# SolarTracker-EagleProject.net
KiCad netlist of a schematic drawn in EAGLE
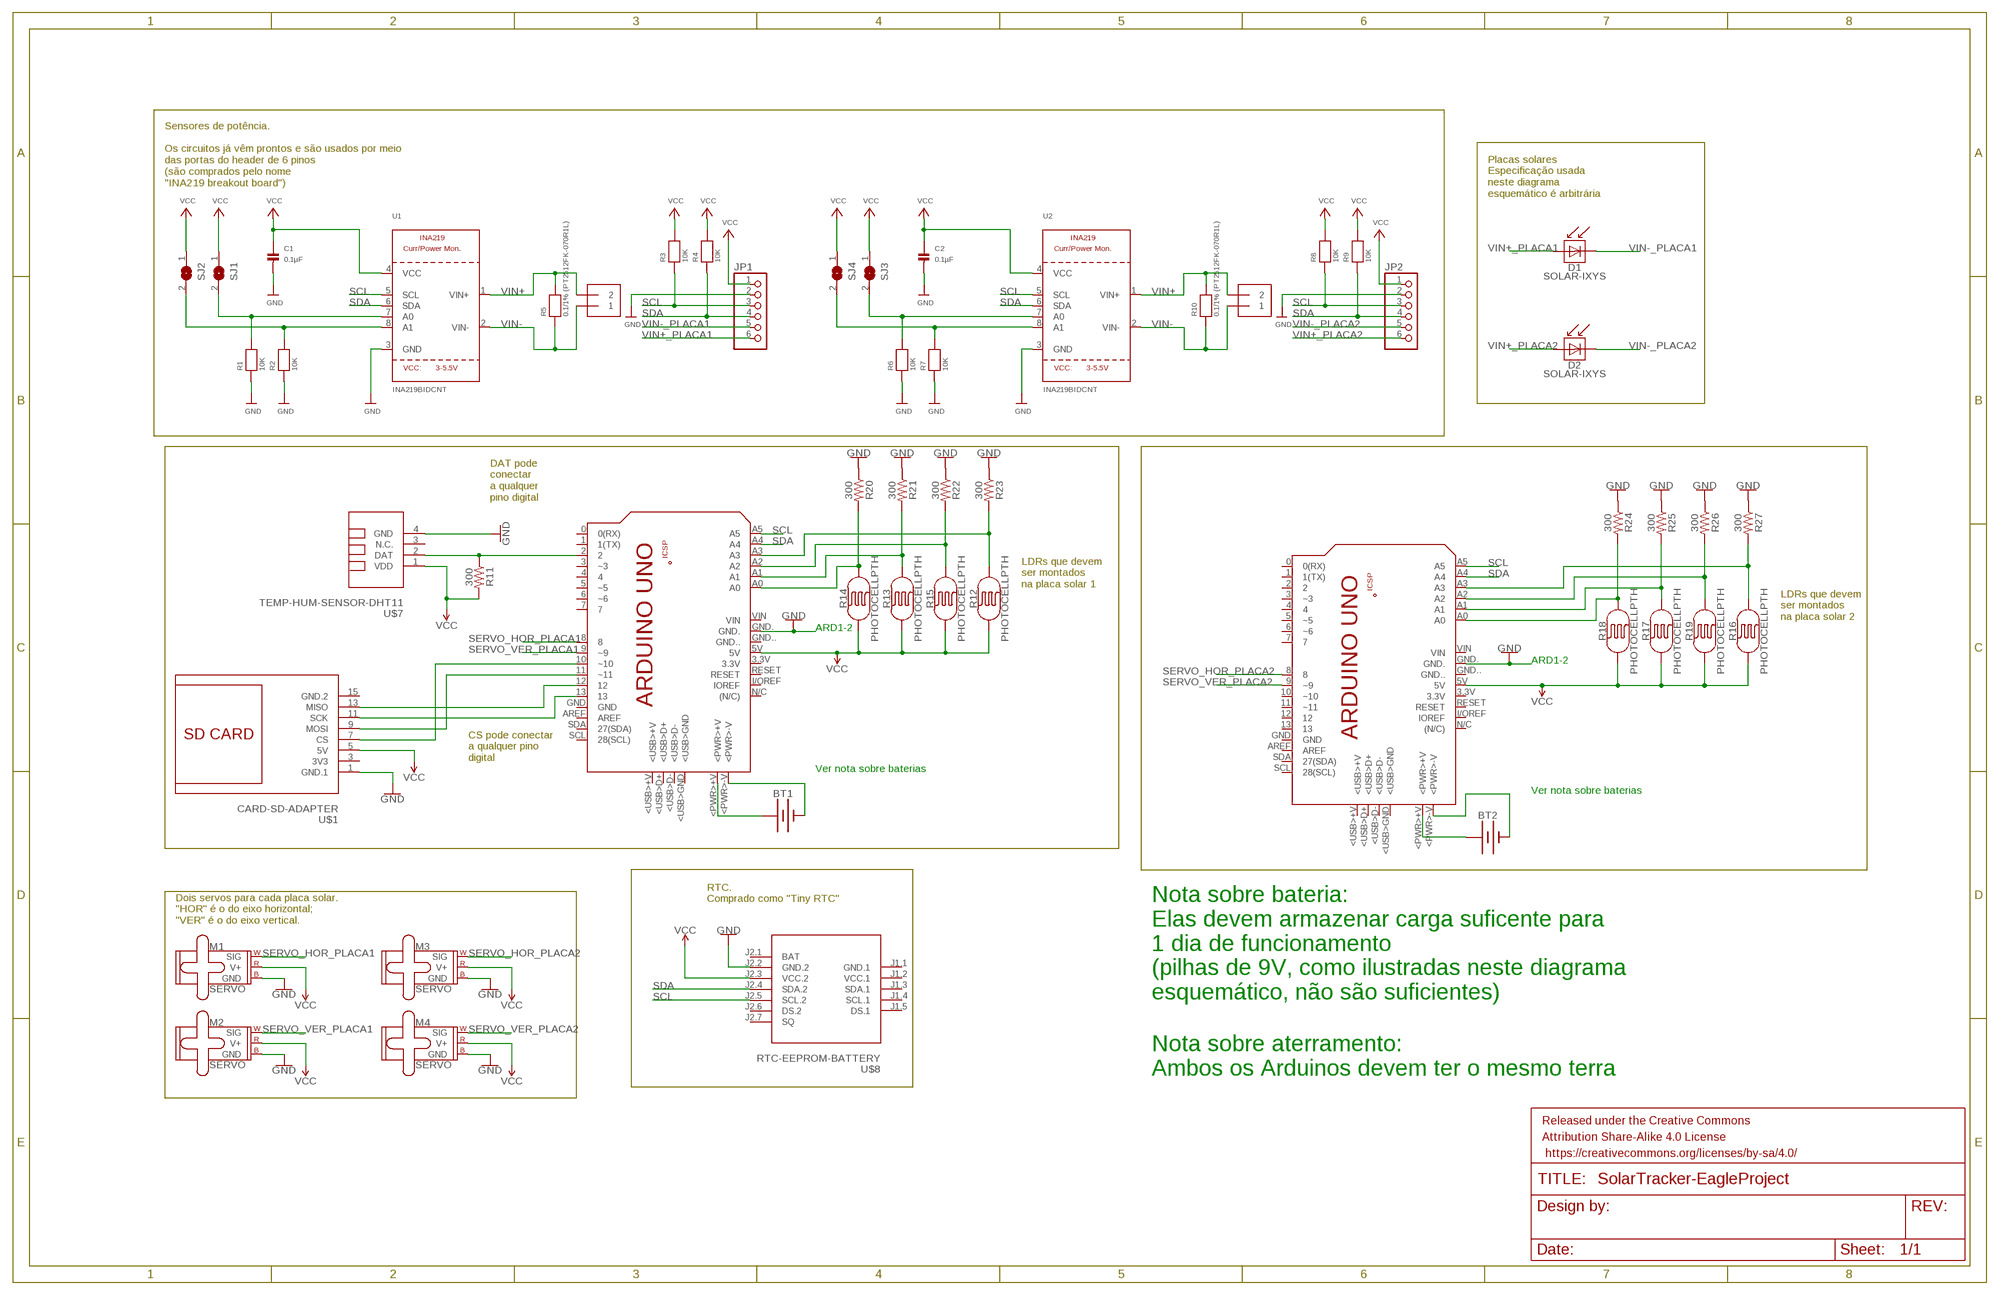
[diagram p0: schematic, sheet 1]

(export (version "E")
  (design (tool "Eeschema 10.0.6"))
  (components
    (comp (ref "BT1")
      (value "BATTERY-9V")
      (footprint "eagle-import:BATTCON_9V")
      (libsource (lib "eagle-import") (part "BATTERY-9V"))
    )
    (comp (ref "BT2")
      (value "BATTERY-9V")
      (footprint "eagle-import:BATTCON_9V")
      (libsource (lib "eagle-import") (part "BATTERY-9V"))
    )
    (comp (ref "C1")
      (value "0.1µF")
      (footprint "eagle-import:0805")
      (libsource (lib "eagle-import") (part "CAP_CERAMIC0805"))
    )
    (comp (ref "C2")
      (value "0.1µF")
      (footprint "eagle-import:0805")
      (libsource (lib "eagle-import") (part "CAP_CERAMIC0805"))
    )
    (comp (ref "D1")
      (value "SOLAR-IXYS")
      (footprint "eagle-import:SOIC-8")
      (libsource (lib "eagle-import") (part "SOLAR-IXYS"))
    )
    (comp (ref "D2")
      (value "SOLAR-IXYS")
      (footprint "eagle-import:SOIC-8")
      (libsource (lib "eagle-import") (part "SOLAR-IXYS"))
    )
    (comp (ref "FRAME1")
      (value "FRAME-LETTER")
      (footprint "eagle-import:CREATIVE_COMMONS")
      (libsource (lib "eagle-import") (part "FRAME-LETTER"))
    )
    (comp (ref "J1")
      (value "TERMBLOCK_1X2-3.5MM")
      (footprint "eagle-import:1X2-3.5MM")
      (libsource (lib "eagle-import") (part "TERMBLOCK_1X2-3.5MM"))
    )
    (comp (ref "J2")
      (value "TERMBLOCK_1X2-3.5MM")
      (footprint "eagle-import:1X2-3.5MM")
      (libsource (lib "eagle-import") (part "TERMBLOCK_1X2-3.5MM"))
    )
    (comp (ref "JP1")
      (value "HEADER-1X670MIL")
      (footprint "eagle-import:1X06_ROUND_70")
      (libsource (lib "eagle-import") (part "HEADER-1X670MIL"))
    )
    (comp (ref "JP2")
      (value "HEADER-1X670MIL")
      (footprint "eagle-import:1X06_ROUND_70")
      (libsource (lib "eagle-import") (part "HEADER-1X670MIL"))
    )
    (comp (ref "M1")
      (value "SERVO")
      (footprint "eagle-import:1X03")
      (libsource (lib "eagle-import") (part "SERVO"))
    )
    (comp (ref "M2")
      (value "SERVO")
      (footprint "eagle-import:1X03")
      (libsource (lib "eagle-import") (part "SERVO"))
    )
    (comp (ref "M3")
      (value "SERVO")
      (footprint "eagle-import:1X03")
      (libsource (lib "eagle-import") (part "SERVO"))
    )
    (comp (ref "M4")
      (value "SERVO")
      (footprint "eagle-import:1X03")
      (libsource (lib "eagle-import") (part "SERVO"))
    )
    (comp (ref "PCB1")
      (value "ARDUINO_UNO")
      (footprint "eagle-import:ARDUINO_UNO")
      (libsource (lib "eagle-import") (part "ARDUINO_UNO"))
    )
    (comp (ref "PCB2")
      (value "ARDUINO_UNO")
      (footprint "eagle-import:ARDUINO_UNO")
      (libsource (lib "eagle-import") (part "ARDUINO_UNO"))
    )
    (comp (ref "R1")
      (value "10K")
      (footprint "eagle-import:0805")
      (libsource (lib "eagle-import") (part "RESISTOR0805"))
    )
    (comp (ref "R2")
      (value "10K")
      (footprint "eagle-import:0805")
      (libsource (lib "eagle-import") (part "RESISTOR0805"))
    )
    (comp (ref "R3")
      (value "10K")
      (footprint "eagle-import:0805")
      (libsource (lib "eagle-import") (part "RESISTOR0805"))
    )
    (comp (ref "R4")
      (value "10K")
      (footprint "eagle-import:0805")
      (libsource (lib "eagle-import") (part "RESISTOR0805"))
    )
    (comp (ref "R5")
      (value "0.1/1% (PT2512FK-070R1L)")
      (footprint "eagle-import:2512")
      (libsource (lib "eagle-import") (part "RESISTOR2512"))
    )
    (comp (ref "R6")
      (value "10K")
      (footprint "eagle-import:0805")
      (libsource (lib "eagle-import") (part "RESISTOR0805"))
    )
    (comp (ref "R7")
      (value "10K")
      (footprint "eagle-import:0805")
      (libsource (lib "eagle-import") (part "RESISTOR0805"))
    )
    (comp (ref "R8")
      (value "10K")
      (footprint "eagle-import:0805")
      (libsource (lib "eagle-import") (part "RESISTOR0805"))
    )
    (comp (ref "R9")
      (value "10K")
      (footprint "eagle-import:0805")
      (libsource (lib "eagle-import") (part "RESISTOR0805"))
    )
    (comp (ref "R10")
      (value "0.1/1% (PT2512FK-070R1L)")
      (footprint "eagle-import:2512")
      (libsource (lib "eagle-import") (part "RESISTOR2512"))
    )
    (comp (ref "R11")
      (value "300")
      (footprint "eagle-import:0603")
      (libsource (lib "eagle-import") (part "300OHM-0603-1/10W-1%"))
    )
    (comp (ref "R12")
      (value "PHOTOCELLPTH")
      (footprint "eagle-import:PHOTOCELL")
      (libsource (lib "eagle-import") (part "PHOTOCELLPTH"))
    )
    (comp (ref "R13")
      (value "PHOTOCELLPTH")
      (footprint "eagle-import:PHOTOCELL")
      (libsource (lib "eagle-import") (part "PHOTOCELLPTH"))
    )
    (comp (ref "R14")
      (value "PHOTOCELLPTH")
      (footprint "eagle-import:PHOTOCELL")
      (libsource (lib "eagle-import") (part "PHOTOCELLPTH"))
    )
    (comp (ref "R15")
      (value "PHOTOCELLPTH")
      (footprint "eagle-import:PHOTOCELL")
      (libsource (lib "eagle-import") (part "PHOTOCELLPTH"))
    )
    (comp (ref "R16")
      (value "PHOTOCELLPTH")
      (footprint "eagle-import:PHOTOCELL")
      (libsource (lib "eagle-import") (part "PHOTOCELLPTH"))
    )
    (comp (ref "R17")
      (value "PHOTOCELLPTH")
      (footprint "eagle-import:PHOTOCELL")
      (libsource (lib "eagle-import") (part "PHOTOCELLPTH"))
    )
    (comp (ref "R18")
      (value "PHOTOCELLPTH")
      (footprint "eagle-import:PHOTOCELL")
      (libsource (lib "eagle-import") (part "PHOTOCELLPTH"))
    )
    (comp (ref "R19")
      (value "PHOTOCELLPTH")
      (footprint "eagle-import:PHOTOCELL")
      (libsource (lib "eagle-import") (part "PHOTOCELLPTH"))
    )
    (comp (ref "R20")
      (value "300")
      (footprint "eagle-import:0603")
      (libsource (lib "eagle-import") (part "300OHM-0603-1/10W-1%"))
    )
    (comp (ref "R21")
      (value "300")
      (footprint "eagle-import:0603")
      (libsource (lib "eagle-import") (part "300OHM-0603-1/10W-1%"))
    )
    (comp (ref "R22")
      (value "300")
      (footprint "eagle-import:0603")
      (libsource (lib "eagle-import") (part "300OHM-0603-1/10W-1%"))
    )
    (comp (ref "R23")
      (value "300")
      (footprint "eagle-import:0603")
      (libsource (lib "eagle-import") (part "300OHM-0603-1/10W-1%"))
    )
    (comp (ref "R24")
      (value "300")
      (footprint "eagle-import:0603")
      (libsource (lib "eagle-import") (part "300OHM-0603-1/10W-1%"))
    )
    (comp (ref "R25")
      (value "300")
      (footprint "eagle-import:0603")
      (libsource (lib "eagle-import") (part "300OHM-0603-1/10W-1%"))
    )
    (comp (ref "R26")
      (value "300")
      (footprint "eagle-import:0603")
      (libsource (lib "eagle-import") (part "300OHM-0603-1/10W-1%"))
    )
    (comp (ref "R27")
      (value "300")
      (footprint "eagle-import:0603")
      (libsource (lib "eagle-import") (part "300OHM-0603-1/10W-1%"))
    )
    (comp (ref "SJ1")
      (value "SOLDERJUMPERREFLOW_NOPASTE")
      (footprint "eagle-import:SOLDERJUMPER_REFLOW_NOPASTE")
      (libsource (lib "eagle-import") (part "SOLDERJUMPERREFLOW_NOPASTE"))
    )
    (comp (ref "SJ2")
      (value "SOLDERJUMPERREFLOW_NOPASTE")
      (footprint "eagle-import:SOLDERJUMPER_REFLOW_NOPASTE")
      (libsource (lib "eagle-import") (part "SOLDERJUMPERREFLOW_NOPASTE"))
    )
    (comp (ref "SJ3")
      (value "SOLDERJUMPERREFLOW_NOPASTE")
      (footprint "eagle-import:SOLDERJUMPER_REFLOW_NOPASTE")
      (libsource (lib "eagle-import") (part "SOLDERJUMPERREFLOW_NOPASTE"))
    )
    (comp (ref "SJ4")
      (value "SOLDERJUMPERREFLOW_NOPASTE")
      (footprint "eagle-import:SOLDERJUMPER_REFLOW_NOPASTE")
      (libsource (lib "eagle-import") (part "SOLDERJUMPERREFLOW_NOPASTE"))
    )
    (comp (ref "U$1")
      (value "CARD-SD-ADAPTER")
      (footprint "eagle-import:CARD-SD-ADAPTER")
      (libsource (lib "eagle-import") (part "CARD-SD-ADAPTER"))
    )
    (comp (ref "U$7")
      (value "TEMP-HUM-SENSOR-DHT11")
      (footprint "eagle-import:TEMP-HUM-SENSOR-DHT11")
      (libsource (lib "eagle-import") (part "TEMP-HUM-SENSOR-DHT11"))
    )
    (comp (ref "U$8")
      (value "RTC-EEPROM-BATTERY")
      (footprint "eagle-import:RTC-EEPROM-BATTERY")
      (libsource (lib "eagle-import") (part "RTC-EEPROM-BATTERY"))
    )
    (comp (ref "U1")
      (value "INA219BIDCNT")
      (footprint "eagle-import:SOT23-8")
      (libsource (lib "eagle-import") (part "INA219"))
    )
    (comp (ref "U2")
      (value "INA219BIDCNT")
      (footprint "eagle-import:SOT23-8")
      (libsource (lib "eagle-import") (part "INA219"))
    )
  )
  (nets
    (net (code "1") (name "/3V3") (class "Default")
      (node (ref "U$1") (pin "3") (pinfunction "3V3_3") (pintype "power_in"))
    )
    (net (code "2") (name "/GND.1") (class "Default")
      (node (ref "U$8") (pin "J1.1") (pinfunction "GND.1_J1.1") (pintype "power_in"))
    )
    (net (code "3") (name "/GND.2") (class "Default")
      (node (ref "U$1") (pin "15") (pinfunction "GND.2_15") (pintype "power_in"))
    )
    (net (code "4") (name "/SCL") (class "Default")
      (node (ref "JP1") (pin "3") (pinfunction "3_3") (pintype "passive"))
      (node (ref "JP2") (pin "3") (pinfunction "3_3") (pintype "passive"))
      (node (ref "PCB1") (pin "A5") (pinfunction "A5_A5") (pintype "bidirectional"))
      (node (ref "PCB2") (pin "A5") (pinfunction "A5_A5") (pintype "bidirectional"))
      (node (ref "R3") (pin "1") (pinfunction "1_1") (pintype "passive"))
      (node (ref "R8") (pin "1") (pinfunction "1_1") (pintype "passive"))
      (node (ref "U$8") (pin "J2.5") (pinfunction "SCL.2_J2.5") (pintype "bidirectional"))
      (node (ref "U1") (pin "5") (pinfunction "SCL_5") (pintype "bidirectional"))
      (node (ref "U2") (pin "5") (pinfunction "SCL_5") (pintype "bidirectional"))
    )
    (net (code "5") (name "/SDA") (class "Default")
      (node (ref "JP1") (pin "4") (pinfunction "4_4") (pintype "passive"))
      (node (ref "JP2") (pin "4") (pinfunction "4_4") (pintype "passive"))
      (node (ref "PCB1") (pin "A4") (pinfunction "A4_A4") (pintype "bidirectional"))
      (node (ref "PCB2") (pin "A4") (pinfunction "A4_A4") (pintype "bidirectional"))
      (node (ref "R4") (pin "1") (pinfunction "1_1") (pintype "passive"))
      (node (ref "R9") (pin "1") (pinfunction "1_1") (pintype "passive"))
      (node (ref "U$8") (pin "J2.4") (pinfunction "SDA.2_J2.4") (pintype "bidirectional"))
      (node (ref "U1") (pin "6") (pinfunction "SDA_6") (pintype "bidirectional"))
      (node (ref "U2") (pin "6") (pinfunction "SDA_6") (pintype "bidirectional"))
    )
    (net (code "6") (name "/SERVO_HOR_PLACA1") (class "Default")
      (node (ref "M1") (pin "1") (pinfunction "SIG_1") (pintype "bidirectional"))
      (node (ref "PCB1") (pin "8") (pinfunction "8_8") (pintype "bidirectional"))
    )
    (net (code "7") (name "/SERVO_HOR_PLACA2") (class "Default")
      (node (ref "M3") (pin "1") (pinfunction "SIG_1") (pintype "bidirectional"))
      (node (ref "PCB2") (pin "8") (pinfunction "8_8") (pintype "bidirectional"))
    )
    (net (code "8") (name "/SERVO_VER_PLACA1") (class "Default")
      (node (ref "M2") (pin "1") (pinfunction "SIG_1") (pintype "bidirectional"))
      (node (ref "PCB1") (pin "9") (pinfunction "~{9}_9") (pintype "bidirectional"))
    )
    (net (code "9") (name "/SERVO_VER_PLACA2") (class "Default")
      (node (ref "M4") (pin "1") (pinfunction "SIG_1") (pintype "bidirectional"))
      (node (ref "PCB2") (pin "9") (pinfunction "~{9}_9") (pintype "bidirectional"))
    )
    (net (code "10") (name "/VCC.1") (class "Default")
      (node (ref "U$8") (pin "J1.2") (pinfunction "VCC.1_J1.2") (pintype "power_in"))
    )
    (net (code "11") (name "/VIN+") (class "Default")
      (node (ref "J1") (pin "2") (pinfunction "2_2") (pintype "passive"))
      (node (ref "J2") (pin "2") (pinfunction "2_2") (pintype "passive"))
      (node (ref "R10") (pin "2") (pinfunction "2_2") (pintype "passive"))
      (node (ref "R5") (pin "2") (pinfunction "2_2") (pintype "passive"))
      (node (ref "U1") (pin "1") (pinfunction "VIN+_1") (pintype "bidirectional"))
      (node (ref "U2") (pin "1") (pinfunction "VIN+_1") (pintype "bidirectional"))
    )
    (net (code "12") (name "/VIN+_PLACA1") (class "Default")
      (node (ref "D1") (pin "8") (pinfunction "A_8") (pintype "passive"))
      (node (ref "JP1") (pin "6") (pinfunction "6_6") (pintype "passive"))
    )
    (net (code "13") (name "/VIN+_PLACA2") (class "Default")
      (node (ref "D2") (pin "8") (pinfunction "A_8") (pintype "passive"))
      (node (ref "JP2") (pin "6") (pinfunction "6_6") (pintype "passive"))
    )
    (net (code "14") (name "/VIN-") (class "Default")
      (node (ref "J1") (pin "1") (pinfunction "1_1") (pintype "passive"))
      (node (ref "J2") (pin "1") (pinfunction "1_1") (pintype "passive"))
      (node (ref "R10") (pin "1") (pinfunction "1_1") (pintype "passive"))
      (node (ref "R5") (pin "1") (pinfunction "1_1") (pintype "passive"))
      (node (ref "U1") (pin "2") (pinfunction "VIN-_2") (pintype "bidirectional"))
      (node (ref "U2") (pin "2") (pinfunction "VIN-_2") (pintype "bidirectional"))
    )
    (net (code "15") (name "/VIN-_PLACA1") (class "Default")
      (node (ref "D1") (pin "5") (pinfunction "C_5") (pintype "passive"))
      (node (ref "JP1") (pin "5") (pinfunction "5_5") (pintype "passive"))
    )
    (net (code "16") (name "/VIN-_PLACA2") (class "Default")
      (node (ref "D2") (pin "5") (pinfunction "C_5") (pintype "passive"))
      (node (ref "JP2") (pin "5") (pinfunction "5_5") (pintype "passive"))
    )
    (net (code "17") (name "GND") (class "Default")
      (node (ref "C1") (pin "2") (pinfunction "P$2_2") (pintype "passive"))
      (node (ref "C2") (pin "2") (pinfunction "P$2_2") (pintype "passive"))
      (node (ref "JP1") (pin "2") (pinfunction "2_2") (pintype "passive"))
      (node (ref "JP2") (pin "2") (pinfunction "2_2") (pintype "passive"))
      (node (ref "M1") (pin "3") (pinfunction "GND_3") (pintype "bidirectional"))
      (node (ref "M2") (pin "3") (pinfunction "GND_3") (pintype "bidirectional"))
      (node (ref "M3") (pin "3") (pinfunction "GND_3") (pintype "bidirectional"))
      (node (ref "M4") (pin "3") (pinfunction "GND_3") (pintype "bidirectional"))
      (node (ref "PCB1") (pin "GND.") (pinfunction "GND._GND.") (pintype "bidirectional"))
      (node (ref "PCB2") (pin "GND.") (pinfunction "GND._GND.") (pintype "bidirectional"))
      (node (ref "R1") (pin "1") (pinfunction "1_1") (pintype "passive"))
      (node (ref "R2") (pin "1") (pinfunction "1_1") (pintype "passive"))
      (node (ref "R20") (pin "1") (pinfunction "1_1") (pintype "passive"))
      (node (ref "R21") (pin "1") (pinfunction "1_1") (pintype "passive"))
      (node (ref "R22") (pin "1") (pinfunction "1_1") (pintype "passive"))
      (node (ref "R23") (pin "1") (pinfunction "1_1") (pintype "passive"))
      (node (ref "R24") (pin "1") (pinfunction "1_1") (pintype "passive"))
      (node (ref "R25") (pin "1") (pinfunction "1_1") (pintype "passive"))
      (node (ref "R26") (pin "1") (pinfunction "1_1") (pintype "passive"))
      (node (ref "R27") (pin "1") (pinfunction "1_1") (pintype "passive"))
      (node (ref "R6") (pin "1") (pinfunction "1_1") (pintype "passive"))
      (node (ref "R7") (pin "1") (pinfunction "1_1") (pintype "passive"))
      (node (ref "U$1") (pin "1") (pinfunction "GND.1_1") (pintype "power_in"))
      (node (ref "U$7") (pin "4") (pinfunction "GND_4") (pintype "power_in"))
      (node (ref "U$8") (pin "J2.2") (pinfunction "GND.2_J2.2") (pintype "power_in"))
      (node (ref "U1") (pin "3") (pinfunction "GND_3") (pintype "bidirectional"))
      (node (ref "U2") (pin "3") (pinfunction "GND_3") (pintype "bidirectional"))
    )
    (net (code "18") (name "Net-(BT1-Pad+)") (class "Default")
      (node (ref "BT1") (pin "+") (pinfunction "+_+") (pintype "power_in"))
      (node (ref "PCB1") (pin "<PWR>+V") (pinfunction "<PWR>+V_<PWR>+V") (pintype "bidirectional"))
    )
    (net (code "19") (name "Net-(BT1-Pad-)") (class "Default")
      (node (ref "BT1") (pin "-") (pinfunction "-_-") (pintype "power_in"))
      (node (ref "PCB1") (pin "<PWR>-V") (pinfunction "<PWR>-V_<PWR>-V") (pintype "bidirectional"))
    )
    (net (code "20") (name "Net-(BT2-Pad+)") (class "Default")
      (node (ref "BT2") (pin "+") (pinfunction "+_+") (pintype "power_in"))
      (node (ref "PCB2") (pin "<PWR>+V") (pinfunction "<PWR>+V_<PWR>+V") (pintype "bidirectional"))
    )
    (net (code "21") (name "Net-(BT2-Pad-)") (class "Default")
      (node (ref "BT2") (pin "-") (pinfunction "-_-") (pintype "power_in"))
      (node (ref "PCB2") (pin "<PWR>-V") (pinfunction "<PWR>-V_<PWR>-V") (pintype "bidirectional"))
    )
    (net (code "22") (name "Net-(PCB1-~{10})") (class "Default")
      (node (ref "PCB1") (pin "10") (pinfunction "~{10}_10") (pintype "bidirectional"))
      (node (ref "U$1") (pin "7") (pinfunction "CS_7") (pintype "bidirectional"))
    )
    (net (code "23") (name "Net-(PCB1-~{11})") (class "Default")
      (node (ref "PCB1") (pin "11") (pinfunction "~{11}_11") (pintype "bidirectional"))
      (node (ref "U$1") (pin "9") (pinfunction "MOSI_9") (pintype "bidirectional"))
    )
    (net (code "24") (name "Net-(R12-P$2)") (class "Default")
      (node (ref "PCB1") (pin "A3") (pinfunction "A3_A3") (pintype "bidirectional"))
      (node (ref "R12") (pin "2") (pinfunction "P$2_2") (pintype "bidirectional"))
      (node (ref "R23") (pin "2") (pinfunction "2_2") (pintype "passive"))
    )
    (net (code "25") (name "Net-(R13-P$2)") (class "Default")
      (node (ref "PCB1") (pin "A1") (pinfunction "A1_A1") (pintype "bidirectional"))
      (node (ref "R13") (pin "2") (pinfunction "P$2_2") (pintype "bidirectional"))
      (node (ref "R21") (pin "2") (pinfunction "2_2") (pintype "passive"))
    )
    (net (code "26") (name "Net-(R14-P$2)") (class "Default")
      (node (ref "PCB1") (pin "A0") (pinfunction "A0_A0") (pintype "bidirectional"))
      (node (ref "R14") (pin "2") (pinfunction "P$2_2") (pintype "bidirectional"))
      (node (ref "R20") (pin "2") (pinfunction "2_2") (pintype "passive"))
    )
    (net (code "27") (name "Net-(R15-P$2)") (class "Default")
      (node (ref "PCB1") (pin "A2") (pinfunction "A2_A2") (pintype "bidirectional"))
      (node (ref "R15") (pin "2") (pinfunction "P$2_2") (pintype "bidirectional"))
      (node (ref "R22") (pin "2") (pinfunction "2_2") (pintype "passive"))
    )
    (net (code "28") (name "Net-(R16-P$2)") (class "Default")
      (node (ref "PCB2") (pin "A3") (pinfunction "A3_A3") (pintype "bidirectional"))
      (node (ref "R16") (pin "2") (pinfunction "P$2_2") (pintype "bidirectional"))
      (node (ref "R27") (pin "2") (pinfunction "2_2") (pintype "passive"))
    )
    (net (code "29") (name "Net-(R17-P$2)") (class "Default")
      (node (ref "PCB2") (pin "A1") (pinfunction "A1_A1") (pintype "bidirectional"))
      (node (ref "R17") (pin "2") (pinfunction "P$2_2") (pintype "bidirectional"))
      (node (ref "R25") (pin "2") (pinfunction "2_2") (pintype "passive"))
    )
    (net (code "30") (name "Net-(R18-P$2)") (class "Default")
      (node (ref "PCB2") (pin "A0") (pinfunction "A0_A0") (pintype "bidirectional"))
      (node (ref "R18") (pin "2") (pinfunction "P$2_2") (pintype "bidirectional"))
      (node (ref "R24") (pin "2") (pinfunction "2_2") (pintype "passive"))
    )
    (net (code "31") (name "Net-(R19-P$2)") (class "Default")
      (node (ref "PCB2") (pin "A2") (pinfunction "A2_A2") (pintype "bidirectional"))
      (node (ref "R19") (pin "2") (pinfunction "P$2_2") (pintype "bidirectional"))
      (node (ref "R26") (pin "2") (pinfunction "2_2") (pintype "passive"))
    )
    (net (code "32") (name "Net-(U$1-MISO)") (class "Default")
      (node (ref "PCB1") (pin "12") (pinfunction "12_12") (pintype "bidirectional"))
      (node (ref "U$1") (pin "13") (pinfunction "MISO_13") (pintype "bidirectional"))
    )
    (net (code "33") (name "Net-(U$1-SCK)") (class "Default")
      (node (ref "PCB1") (pin "13") (pinfunction "13_13") (pintype "bidirectional"))
      (node (ref "U$1") (pin "11") (pinfunction "SCK_11") (pintype "bidirectional"))
    )
    (net (code "34") (name "Net-(U$7-DAT)") (class "Default")
      (node (ref "PCB1") (pin "2") (pinfunction "2_2") (pintype "bidirectional"))
      (node (ref "R11") (pin "1") (pinfunction "1_1") (pintype "passive"))
      (node (ref "U$7") (pin "2") (pinfunction "DAT_2") (pintype "bidirectional"))
    )
    (net (code "35") (name "Net-(U1-A0)") (class "Default")
      (node (ref "R1") (pin "2") (pinfunction "2_2") (pintype "passive"))
      (node (ref "SJ1") (pin "2") (pinfunction "2_2") (pintype "passive"))
      (node (ref "U1") (pin "7") (pinfunction "A0_7") (pintype "bidirectional"))
    )
    (net (code "36") (name "Net-(U1-A1)") (class "Default")
      (node (ref "R2") (pin "2") (pinfunction "2_2") (pintype "passive"))
      (node (ref "SJ2") (pin "2") (pinfunction "2_2") (pintype "passive"))
      (node (ref "U1") (pin "8") (pinfunction "A1_8") (pintype "bidirectional"))
    )
    (net (code "37") (name "Net-(U2-A0)") (class "Default")
      (node (ref "R6") (pin "2") (pinfunction "2_2") (pintype "passive"))
      (node (ref "SJ3") (pin "2") (pinfunction "2_2") (pintype "passive"))
      (node (ref "U2") (pin "7") (pinfunction "A0_7") (pintype "bidirectional"))
    )
    (net (code "38") (name "Net-(U2-A1)") (class "Default")
      (node (ref "R7") (pin "2") (pinfunction "2_2") (pintype "passive"))
      (node (ref "SJ4") (pin "2") (pinfunction "2_2") (pintype "passive"))
      (node (ref "U2") (pin "8") (pinfunction "A1_8") (pintype "bidirectional"))
    )
    (net (code "39") (name "VCC") (class "Default")
      (node (ref "C1") (pin "1") (pinfunction "P$1_1") (pintype "passive"))
      (node (ref "C2") (pin "1") (pinfunction "P$1_1") (pintype "passive"))
      (node (ref "JP1") (pin "1") (pinfunction "1_1") (pintype "passive"))
      (node (ref "JP2") (pin "1") (pinfunction "1_1") (pintype "passive"))
      (node (ref "M1") (pin "2") (pinfunction "V+_2") (pintype "bidirectional"))
      (node (ref "M2") (pin "2") (pinfunction "V+_2") (pintype "bidirectional"))
      (node (ref "M3") (pin "2") (pinfunction "V+_2") (pintype "bidirectional"))
      (node (ref "M4") (pin "2") (pinfunction "V+_2") (pintype "bidirectional"))
      (node (ref "PCB1") (pin "5V") (pinfunction "5V_5V") (pintype "bidirectional"))
      (node (ref "PCB2") (pin "5V") (pinfunction "5V_5V") (pintype "bidirectional"))
      (node (ref "R11") (pin "2") (pinfunction "2_2") (pintype "passive"))
      (node (ref "R12") (pin "1") (pinfunction "P$1_1") (pintype "bidirectional"))
      (node (ref "R13") (pin "1") (pinfunction "P$1_1") (pintype "bidirectional"))
      (node (ref "R14") (pin "1") (pinfunction "P$1_1") (pintype "bidirectional"))
      (node (ref "R15") (pin "1") (pinfunction "P$1_1") (pintype "bidirectional"))
      (node (ref "R16") (pin "1") (pinfunction "P$1_1") (pintype "bidirectional"))
      (node (ref "R17") (pin "1") (pinfunction "P$1_1") (pintype "bidirectional"))
      (node (ref "R18") (pin "1") (pinfunction "P$1_1") (pintype "bidirectional"))
      (node (ref "R19") (pin "1") (pinfunction "P$1_1") (pintype "bidirectional"))
      (node (ref "R3") (pin "2") (pinfunction "2_2") (pintype "passive"))
      (node (ref "R4") (pin "2") (pinfunction "2_2") (pintype "passive"))
      (node (ref "R8") (pin "2") (pinfunction "2_2") (pintype "passive"))
      (node (ref "R9") (pin "2") (pinfunction "2_2") (pintype "passive"))
      (node (ref "SJ1") (pin "1") (pinfunction "1_1") (pintype "passive"))
      (node (ref "SJ2") (pin "1") (pinfunction "1_1") (pintype "passive"))
      (node (ref "SJ3") (pin "1") (pinfunction "1_1") (pintype "passive"))
      (node (ref "SJ4") (pin "1") (pinfunction "1_1") (pintype "passive"))
      (node (ref "U$1") (pin "5") (pinfunction "5V_5") (pintype "power_in"))
      (node (ref "U$7") (pin "1") (pinfunction "VDD_1") (pintype "power_in"))
      (node (ref "U$8") (pin "J2.3") (pinfunction "VCC.2_J2.3") (pintype "power_in"))
      (node (ref "U1") (pin "4") (pinfunction "VCC_4") (pintype "bidirectional"))
      (node (ref "U2") (pin "4") (pinfunction "VCC_4") (pintype "bidirectional"))
    )
    (net (code "40") (name "unconnected-(PCB1-(N{slash}C)-PadN{slash}C)") (class "Default")
      (node (ref "PCB1") (pin "N/C") (pinfunction "(N/C)_N/C") (pintype "bidirectional"))
    )
    (net (code "41") (name "unconnected-(PCB1-0(RX)-Pad0)") (class "Default")
      (node (ref "PCB1") (pin "0") (pinfunction "0(RX)_0") (pintype "bidirectional"))
    )
    (net (code "42") (name "unconnected-(PCB1-1(TX)-Pad1)") (class "Default")
      (node (ref "PCB1") (pin "1") (pinfunction "1(TX)_1") (pintype "bidirectional"))
    )
    (net (code "43") (name "unconnected-(PCB1-27(SDA)-PadSDA)") (class "Default")
      (node (ref "PCB1") (pin "SDA") (pinfunction "27(SDA)_SDA") (pintype "bidirectional"))
    )
    (net (code "44") (name "unconnected-(PCB1-28(SCL)-PadSCL)") (class "Default")
      (node (ref "PCB1") (pin "SCL") (pinfunction "28(SCL)_SCL") (pintype "bidirectional"))
    )
    (net (code "45") (name "unconnected-(PCB1-IOREF-PadI{slash}OREF)") (class "Default")
      (node (ref "PCB1") (pin "I/OREF") (pinfunction "IOREF_I/OREF") (pintype "bidirectional"))
    )
    (net (code "46") (name "unconnected-(PCB1-Pad+5V)") (class "Default")
      (node (ref "PCB1") (pin "+5V") (pinfunction "+5V_+5V") (pintype "bidirectional"))
    )
    (net (code "47") (name "unconnected-(PCB1-Pad3.3V)") (class "Default")
      (node (ref "PCB1") (pin "3.3V") (pinfunction "3.3V_3.3V") (pintype "bidirectional"))
    )
    (net (code "48") (name "unconnected-(PCB1-Pad4)") (class "Default")
      (node (ref "PCB1") (pin "4") (pinfunction "4_4") (pintype "bidirectional"))
    )
    (net (code "49") (name "unconnected-(PCB1-Pad7)") (class "Default")
      (node (ref "PCB1") (pin "7") (pinfunction "7_7") (pintype "bidirectional"))
    )
    (net (code "50") (name "unconnected-(PCB1-Pad<USB>+V)") (class "Default")
      (node (ref "PCB1") (pin "<USB>+V") (pinfunction "<USB>+V_<USB>+V") (pintype "bidirectional"))
    )
    (net (code "51") (name "unconnected-(PCB1-Pad<USB>D+)") (class "Default")
      (node (ref "PCB1") (pin "<USB>D+") (pinfunction "<USB>D+_<USB>D+") (pintype "bidirectional"))
    )
    (net (code "52") (name "unconnected-(PCB1-Pad<USB>D-)") (class "Default")
      (node (ref "PCB1") (pin "<USB>D-") (pinfunction "<USB>D-_<USB>D-") (pintype "bidirectional"))
    )
    (net (code "53") (name "unconnected-(PCB1-Pad<USB>GND)") (class "Default")
      (node (ref "PCB1") (pin "<USB>GND") (pinfunction "<USB>GND_<USB>GND") (pintype "bidirectional"))
    )
    (net (code "54") (name "unconnected-(PCB1-PadAREF)") (class "Default")
      (node (ref "PCB1") (pin "AREF") (pinfunction "AREF_AREF") (pintype "bidirectional"))
    )
    (net (code "55") (name "unconnected-(PCB1-PadGND)") (class "Default")
      (node (ref "PCB1") (pin "GND") (pinfunction "GND_GND") (pintype "bidirectional"))
    )
    (net (code "56") (name "unconnected-(PCB1-PadGND..)") (class "Default")
      (node (ref "PCB1") (pin "GND..") (pinfunction "GND.._GND..") (pintype "bidirectional"))
    )
    (net (code "57") (name "unconnected-(PCB1-PadGND_)") (class "Default")
      (node (ref "PCB1") (pin "GND_") (pinfunction "GND__GND_") (pintype "bidirectional"))
    )
    (net (code "58") (name "unconnected-(PCB1-PadMISO)") (class "Default")
      (node (ref "PCB1") (pin "MISO") (pinfunction "MISO_MISO") (pintype "bidirectional"))
    )
    (net (code "59") (name "unconnected-(PCB1-PadMOSI)") (class "Default")
      (node (ref "PCB1") (pin "MOSI") (pinfunction "MOSI_MOSI") (pintype "bidirectional"))
    )
    (net (code "60") (name "unconnected-(PCB1-PadRESET)") (class "Default")
      (node (ref "PCB1") (pin "RESET") (pinfunction "RESET_RESET") (pintype "bidirectional"))
    )
    (net (code "61") (name "unconnected-(PCB1-PadRESET.)") (class "Default")
      (node (ref "PCB1") (pin "RESET.") (pinfunction "RESET._RESET.") (pintype "bidirectional"))
    )
    (net (code "62") (name "unconnected-(PCB1-PadSCK)") (class "Default")
      (node (ref "PCB1") (pin "SCK") (pinfunction "SCK_SCK") (pintype "bidirectional"))
    )
    (net (code "63") (name "unconnected-(PCB1-PadVIN)") (class "Default")
      (node (ref "PCB1") (pin "VIN") (pinfunction "VIN_VIN") (pintype "bidirectional"))
    )
    (net (code "64") (name "unconnected-(PCB1-~{3}-Pad3)") (class "Default")
      (node (ref "PCB1") (pin "3") (pinfunction "~{3}_3") (pintype "bidirectional"))
    )
    (net (code "65") (name "unconnected-(PCB1-~{5}-Pad5)") (class "Default")
      (node (ref "PCB1") (pin "5") (pinfunction "~{5}_5") (pintype "bidirectional"))
    )
    (net (code "66") (name "unconnected-(PCB1-~{6}-Pad6)") (class "Default")
      (node (ref "PCB1") (pin "6") (pinfunction "~{6}_6") (pintype "bidirectional"))
    )
    (net (code "67") (name "unconnected-(PCB2-(N{slash}C)-PadN{slash}C)") (class "Default")
      (node (ref "PCB2") (pin "N/C") (pinfunction "(N/C)_N/C") (pintype "bidirectional"))
    )
    (net (code "68") (name "unconnected-(PCB2-0(RX)-Pad0)") (class "Default")
      (node (ref "PCB2") (pin "0") (pinfunction "0(RX)_0") (pintype "bidirectional"))
    )
    (net (code "69") (name "unconnected-(PCB2-1(TX)-Pad1)") (class "Default")
      (node (ref "PCB2") (pin "1") (pinfunction "1(TX)_1") (pintype "bidirectional"))
    )
    (net (code "70") (name "unconnected-(PCB2-27(SDA)-PadSDA)") (class "Default")
      (node (ref "PCB2") (pin "SDA") (pinfunction "27(SDA)_SDA") (pintype "bidirectional"))
    )
    (net (code "71") (name "unconnected-(PCB2-28(SCL)-PadSCL)") (class "Default")
      (node (ref "PCB2") (pin "SCL") (pinfunction "28(SCL)_SCL") (pintype "bidirectional"))
    )
    (net (code "72") (name "unconnected-(PCB2-IOREF-PadI{slash}OREF)") (class "Default")
      (node (ref "PCB2") (pin "I/OREF") (pinfunction "IOREF_I/OREF") (pintype "bidirectional"))
    )
    (net (code "73") (name "unconnected-(PCB2-Pad+5V)") (class "Default")
      (node (ref "PCB2") (pin "+5V") (pinfunction "+5V_+5V") (pintype "bidirectional"))
    )
    (net (code "74") (name "unconnected-(PCB2-Pad2)") (class "Default")
      (node (ref "PCB2") (pin "2") (pinfunction "2_2") (pintype "bidirectional"))
    )
    (net (code "75") (name "unconnected-(PCB2-Pad3.3V)") (class "Default")
      (node (ref "PCB2") (pin "3.3V") (pinfunction "3.3V_3.3V") (pintype "bidirectional"))
    )
    (net (code "76") (name "unconnected-(PCB2-Pad4)") (class "Default")
      (node (ref "PCB2") (pin "4") (pinfunction "4_4") (pintype "bidirectional"))
    )
    (net (code "77") (name "unconnected-(PCB2-Pad7)") (class "Default")
      (node (ref "PCB2") (pin "7") (pinfunction "7_7") (pintype "bidirectional"))
    )
    (net (code "78") (name "unconnected-(PCB2-Pad12)") (class "Default")
      (node (ref "PCB2") (pin "12") (pinfunction "12_12") (pintype "bidirectional"))
    )
    (net (code "79") (name "unconnected-(PCB2-Pad13)") (class "Default")
      (node (ref "PCB2") (pin "13") (pinfunction "13_13") (pintype "bidirectional"))
    )
    (net (code "80") (name "unconnected-(PCB2-Pad<USB>+V)") (class "Default")
      (node (ref "PCB2") (pin "<USB>+V") (pinfunction "<USB>+V_<USB>+V") (pintype "bidirectional"))
    )
    (net (code "81") (name "unconnected-(PCB2-Pad<USB>D+)") (class "Default")
      (node (ref "PCB2") (pin "<USB>D+") (pinfunction "<USB>D+_<USB>D+") (pintype "bidirectional"))
    )
    (net (code "82") (name "unconnected-(PCB2-Pad<USB>D-)") (class "Default")
      (node (ref "PCB2") (pin "<USB>D-") (pinfunction "<USB>D-_<USB>D-") (pintype "bidirectional"))
    )
    (net (code "83") (name "unconnected-(PCB2-Pad<USB>GND)") (class "Default")
      (node (ref "PCB2") (pin "<USB>GND") (pinfunction "<USB>GND_<USB>GND") (pintype "bidirectional"))
    )
    (net (code "84") (name "unconnected-(PCB2-PadAREF)") (class "Default")
      (node (ref "PCB2") (pin "AREF") (pinfunction "AREF_AREF") (pintype "bidirectional"))
    )
    (net (code "85") (name "unconnected-(PCB2-PadGND)") (class "Default")
      (node (ref "PCB2") (pin "GND") (pinfunction "GND_GND") (pintype "bidirectional"))
    )
    (net (code "86") (name "unconnected-(PCB2-PadGND..)") (class "Default")
      (node (ref "PCB2") (pin "GND..") (pinfunction "GND.._GND..") (pintype "bidirectional"))
    )
    (net (code "87") (name "unconnected-(PCB2-PadGND_)") (class "Default")
      (node (ref "PCB2") (pin "GND_") (pinfunction "GND__GND_") (pintype "bidirectional"))
    )
    (net (code "88") (name "unconnected-(PCB2-PadMISO)") (class "Default")
      (node (ref "PCB2") (pin "MISO") (pinfunction "MISO_MISO") (pintype "bidirectional"))
    )
    (net (code "89") (name "unconnected-(PCB2-PadMOSI)") (class "Default")
      (node (ref "PCB2") (pin "MOSI") (pinfunction "MOSI_MOSI") (pintype "bidirectional"))
    )
    (net (code "90") (name "unconnected-(PCB2-PadRESET)") (class "Default")
      (node (ref "PCB2") (pin "RESET") (pinfunction "RESET_RESET") (pintype "bidirectional"))
    )
    (net (code "91") (name "unconnected-(PCB2-PadRESET.)") (class "Default")
      (node (ref "PCB2") (pin "RESET.") (pinfunction "RESET._RESET.") (pintype "bidirectional"))
    )
    (net (code "92") (name "unconnected-(PCB2-PadSCK)") (class "Default")
      (node (ref "PCB2") (pin "SCK") (pinfunction "SCK_SCK") (pintype "bidirectional"))
    )
    (net (code "93") (name "unconnected-(PCB2-PadVIN)") (class "Default")
      (node (ref "PCB2") (pin "VIN") (pinfunction "VIN_VIN") (pintype "bidirectional"))
    )
    (net (code "94") (name "unconnected-(PCB2-~{3}-Pad3)") (class "Default")
      (node (ref "PCB2") (pin "3") (pinfunction "~{3}_3") (pintype "bidirectional"))
    )
    (net (code "95") (name "unconnected-(PCB2-~{5}-Pad5)") (class "Default")
      (node (ref "PCB2") (pin "5") (pinfunction "~{5}_5") (pintype "bidirectional"))
    )
    (net (code "96") (name "unconnected-(PCB2-~{6}-Pad6)") (class "Default")
      (node (ref "PCB2") (pin "6") (pinfunction "~{6}_6") (pintype "bidirectional"))
    )
    (net (code "97") (name "unconnected-(PCB2-~{10}-Pad10)") (class "Default")
      (node (ref "PCB2") (pin "10") (pinfunction "~{10}_10") (pintype "bidirectional"))
    )
    (net (code "98") (name "unconnected-(PCB2-~{11}-Pad11)") (class "Default")
      (node (ref "PCB2") (pin "11") (pinfunction "~{11}_11") (pintype "bidirectional"))
    )
    (net (code "99") (name "unconnected-(U$7-N.C.-Pad3)") (class "Default")
      (node (ref "U$7") (pin "3") (pinfunction "N.C._3") (pintype "passive"))
    )
    (net (code "100") (name "unconnected-(U$8-BAT-PadJ2.1)") (class "Default")
      (node (ref "U$8") (pin "J2.1") (pinfunction "BAT_J2.1") (pintype "bidirectional"))
    )
    (net (code "101") (name "unconnected-(U$8-DS.1-PadJ1.5)") (class "Default")
      (node (ref "U$8") (pin "J1.5") (pinfunction "DS.1_J1.5") (pintype "bidirectional"))
    )
    (net (code "102") (name "unconnected-(U$8-DS.2-PadJ2.6)") (class "Default")
      (node (ref "U$8") (pin "J2.6") (pinfunction "DS.2_J2.6") (pintype "bidirectional"))
    )
    (net (code "103") (name "unconnected-(U$8-SCL.1-PadJ1.4)") (class "Default")
      (node (ref "U$8") (pin "J1.4") (pinfunction "SCL.1_J1.4") (pintype "bidirectional"))
    )
    (net (code "104") (name "unconnected-(U$8-SDA.1-PadJ1.3)") (class "Default")
      (node (ref "U$8") (pin "J1.3") (pinfunction "SDA.1_J1.3") (pintype "bidirectional"))
    )
    (net (code "105") (name "unconnected-(U$8-SQ-PadJ2.7)") (class "Default")
      (node (ref "U$8") (pin "J2.7") (pinfunction "SQ_J2.7") (pintype "bidirectional"))
    )
  )
)
